# schematic.net
KiCad netlist of a schematic drawn in EasyEDA
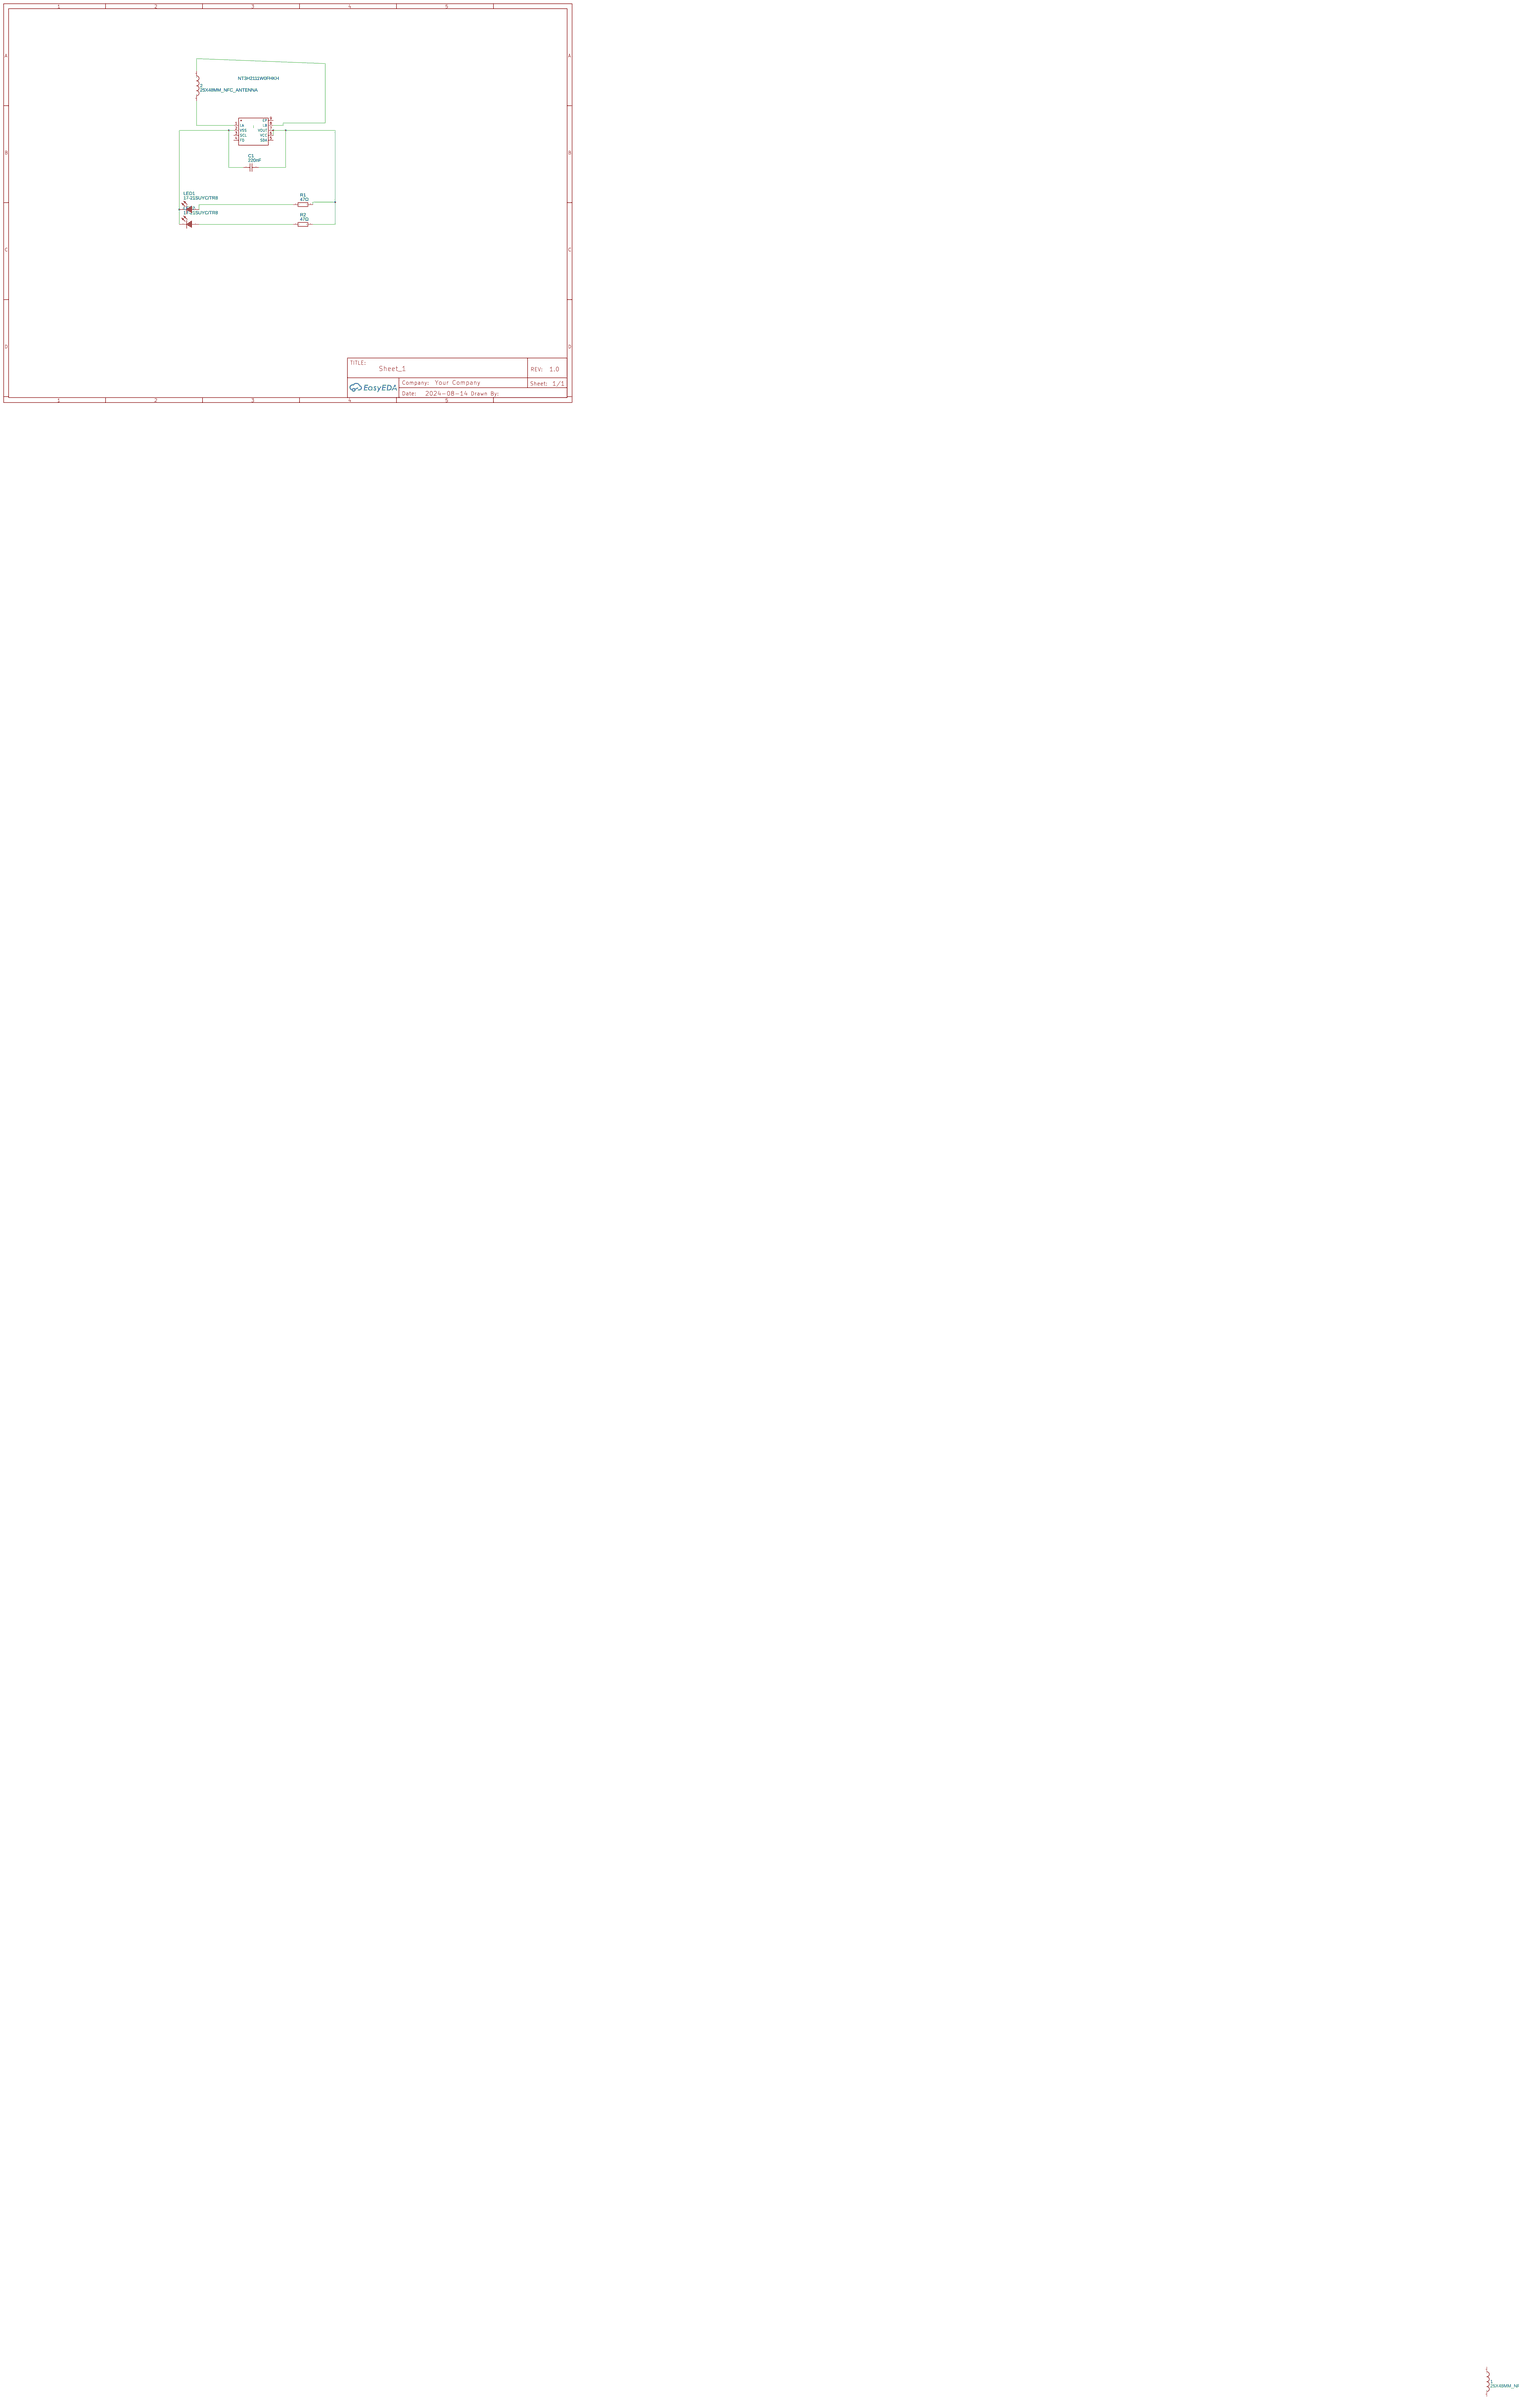
[diagram p0: schematic sheet]

(export (version "E")
  (design (tool "Eeschema 10.0.6"))
  (components
    (comp (ref "1") (value "25X48MM_NFC_ANTENNA") (libsource (lib "") (part "25X48MM_NFC_ANTENNA")))
    (comp (ref "2") (value "25X48MM_NFC_ANTENNA") (libsource (lib "") (part "25X48MM_NFC_ANTENNA")))
    (comp (ref "C1")
      (value "220nF")
      (fields
        (field (name "Manufacturer Part") "CL10B224KA8NNNC")
        (field (name "Manufacturer") "SAMSUNG(三星)")
      )
      (libsource (lib "") (part "CL10B224KA8NNNC"))
    )
    (comp (ref "LED1")
      (value "17-21SUYC/TR8")
      (fields (field (name "Manufacturer Part") "KT-0805黄灯") (field (name "Manufacturer") "KENTO"))
      (libsource (lib "") (part "17-21SUYC/TR8"))
    )
    (comp (ref "LED2")
      (value "17-21SUYC/TR8")
      (fields (field (name "Manufacturer Part") "KT-0805黄灯") (field (name "Manufacturer") "KENTO"))
      (libsource (lib "") (part "17-21SUYC/TR8"))
    )
    (comp (ref "R1")
      (value "47Ω")
      (fields
        (field (name "Manufacturer Part") "0603WAF470JT5E")
        (field (name "Manufacturer") "UNI-ROYAL(厚声)")
      )
      (libsource (lib "") (part "0603WAF470JT5E"))
    )
    (comp (ref "R2")
      (value "47Ω")
      (fields
        (field (name "Manufacturer Part") "0603WAF470JT5E")
        (field (name "Manufacturer") "UNI-ROYAL(厚声)")
      )
      (libsource (lib "") (part "0603WAF470JT5E"))
    )
    (comp (ref "U1")
      (value "NT3H2111W0FHKH")
      (fields (field (name "Manufacturer") "NXP(恩智浦)"))
      (libsource (lib "") (part "NT3H2111W0FHKH"))
    )
  )
  (nets
    (net (code "1") (name "Net-(LED1-+)") (class "Default")
      (node (ref "LED1") (pin "1") (pinfunction "+_1") (pintype "unspecified"))
      (node (ref "R1") (pin "1") (pinfunction "1_1") (pintype "input"))
    )
    (net (code "2") (name "Net-(LED1--)") (class "Default")
      (node (ref "C1") (pin "1") (pinfunction "1_1") (pintype "input"))
      (node (ref "LED1") (pin "2") (pinfunction "-_2") (pintype "unspecified"))
      (node (ref "LED2") (pin "2") (pinfunction "-_2") (pintype "unspecified"))
      (node (ref "U1") (pin "2") (pinfunction "VSS_2") (pintype "unspecified"))
    )
    (net (code "3") (name "Net-(LED2-+)") (class "Default")
      (node (ref "LED2") (pin "1") (pinfunction "+_1") (pintype "unspecified"))
      (node (ref "R2") (pin "1") (pinfunction "1_1") (pintype "input"))
    )
    (net (code "4") (name "Net-(U1-LA)") (class "Default")
      (node (ref "2") (pin "P$2") (pinfunction "P$2_P$2") (pintype "bidirectional"))
      (node (ref "U1") (pin "1") (pinfunction "LA_1") (pintype "unspecified"))
    )
    (net (code "5") (name "Net-(U1-LB)") (class "Default")
      (node (ref "2") (pin "P$1") (pinfunction "P$1_P$1") (pintype "bidirectional"))
      (node (ref "U1") (pin "8") (pinfunction "LB_8") (pintype "unspecified"))
    )
    (net (code "6") (name "Net-(U1-VCC)") (class "Default")
      (node (ref "C1") (pin "2") (pinfunction "2_2") (pintype "input"))
      (node (ref "R1") (pin "2") (pinfunction "2_2") (pintype "input"))
      (node (ref "R2") (pin "2") (pinfunction "2_2") (pintype "input"))
      (node (ref "U1") (pin "6") (pinfunction "VCC_6") (pintype "unspecified"))
      (node (ref "U1") (pin "7") (pinfunction "VOUT_7") (pintype "unspecified"))
    )
    (net (code "7") (name "unconnected-(1-PadP$1)") (class "Default")
      (node (ref "1") (pin "P$1") (pinfunction "P$1_P$1") (pintype "bidirectional"))
    )
    (net (code "8") (name "unconnected-(1-PadP$2)") (class "Default")
      (node (ref "1") (pin "P$2") (pinfunction "P$2_P$2") (pintype "bidirectional"))
    )
    (net (code "9") (name "unconnected-(U1-EP-Pad9)") (class "Default")
      (node (ref "U1") (pin "9") (pinfunction "EP_9") (pintype "unspecified"))
    )
    (net (code "10") (name "unconnected-(U1-FD-Pad4)") (class "Default")
      (node (ref "U1") (pin "4") (pinfunction "FD_4") (pintype "unspecified"))
    )
    (net (code "11") (name "unconnected-(U1-SCL-Pad3)") (class "Default")
      (node (ref "U1") (pin "3") (pinfunction "SCL_3") (pintype "unspecified"))
    )
    (net (code "12") (name "unconnected-(U1-SDA-Pad5)") (class "Default")
      (node (ref "U1") (pin "5") (pinfunction "SDA_5") (pintype "unspecified"))
    )
  )
)
